# DONGLE01.net
KiCad netlist of a schematic drawn in Altium Designer
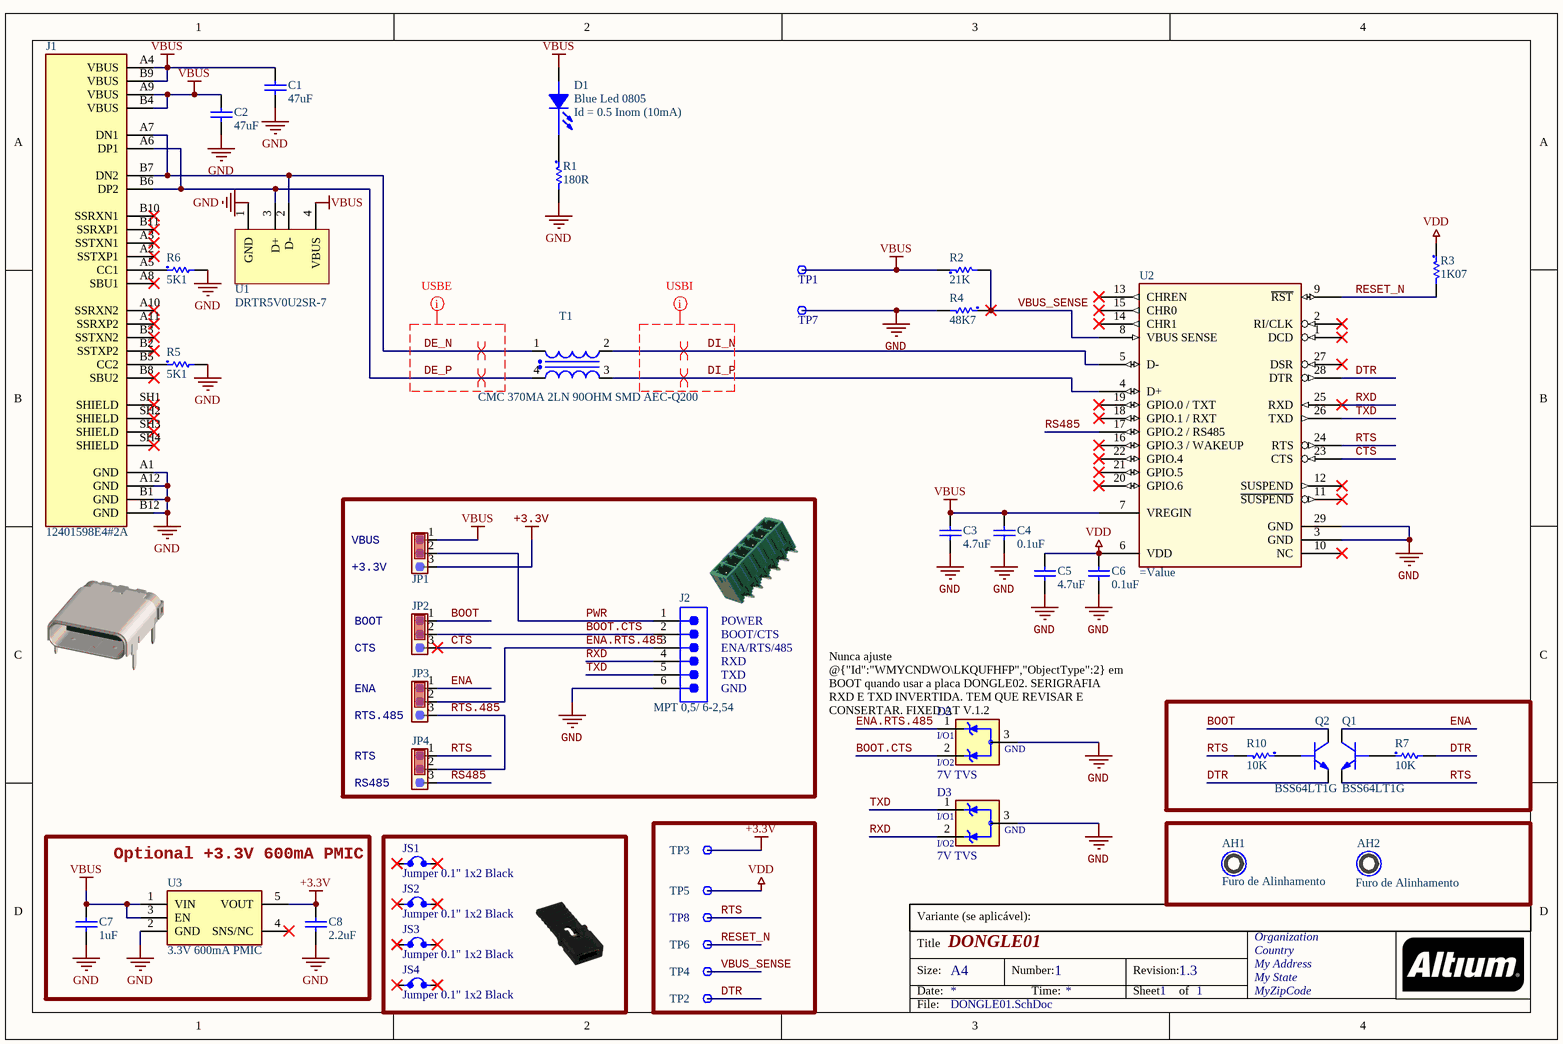
[diagram p0: DONGLE01.SchDoc]

(export (version "E")
  (design (tool "Eeschema 10.0.6"))
  (components
    (comp (ref "AH1")
      (value "Furo de Alinhamento")
      (footprint "AH_2.0MMD")
      (libsource (lib "My_Library") (part "Aligment Hole M2"))
    )
    (comp (ref "AH2")
      (value "Furo de Alinhamento")
      (footprint "AH_2.0MMD")
      (libsource (lib "My_Library") (part "Aligment Hole M2"))
    )
    (comp (ref "C1")
      (value "47uF")
      (footprint "C0805")
      (description "47 µF ±20% 10V Ceramic Capacitor X5R 0805 (2012 Metric)")
      (fields (field (name "MANUFACTURER") "Murata Electronics"))
      (libsource (lib "My_Library") (part "CAP"))
    )
    (comp (ref "C2")
      (value "47uF")
      (footprint "C0805")
      (description "47 µF ±20% 10V Ceramic Capacitor X5R 0805 (2012 Metric)")
      (fields (field (name "MANUFACTURER") "Murata Electronics"))
      (libsource (lib "My_Library") (part "CAP"))
    )
    (comp (ref "C3")
      (value "4.7uF")
      (footprint "C0805")
      (description "4.7 µF ±10% 50V Ceramic Capacitor X7R 0805 (2012 Metric)")
      (fields (field (name "MANUFACTURER") "TDK Corporation"))
      (libsource (lib "My_Library") (part "CAP"))
    )
    (comp (ref "C4")
      (value "0.1uF")
      (footprint "C0805")
      (description "0.1 µF ±10% 100V Ceramic Capacitor X7R 0805 (2012 Metric)")
      (fields (field (name "MANUFACTURER") "Murata Electronics"))
      (libsource (lib "My_Library") (part "CAP"))
    )
    (comp (ref "C5")
      (value "4.7uF")
      (footprint "C0805")
      (description "4.7 µF ±10% 50V Ceramic Capacitor X7R 0805 (2012 Metric)")
      (fields (field (name "MANUFACTURER") "TDK Corporation"))
      (libsource (lib "My_Library") (part "CAP"))
    )
    (comp (ref "C6")
      (value "0.1uF")
      (footprint "C0805")
      (description "0.1 µF ±10% 100V Ceramic Capacitor X7R 0805 (2012 Metric)")
      (fields (field (name "MANUFACTURER") "Murata Electronics"))
      (libsource (lib "My_Library") (part "CAP"))
    )
    (comp (ref "C7")
      (value "1uF")
      (footprint "C0805")
      (description "1 µF ±5% 16V Ceramic Capacitor X7R 0805 (2012 Metric)")
      (fields (field (name "MANUFACTURER") "KEMET"))
      (libsource (lib "My_Library") (part "CAP"))
    )
    (comp (ref "C8")
      (value "2.2uF")
      (footprint "C0805")
      (description "2.2 µF ±5% 16V Ceramic Capacitor X7R 0805 (2012 Metric)")
      (fields (field (name "MANUFACTURER") "KEMET"))
      (libsource (lib "My_Library") (part "CAP"))
    )
    (comp (ref "D1")
      (value "Blue Led 0805")
      (footprint "LED 0805")
      (description "Blue 470nm LED Indication - Discrete 3.2V 0805 (2012 Metric)")
      (fields (field (name "MANUFACTURER") "Würth Elektronik") (field (name "INFO") "Id = 0.5 Inom (10mA)"))
      (libsource (lib "My_Library") (part "LED GREEN 0805"))
    )
    (comp (ref "D2")
      (value "7V TVS")
      (footprint "WE-TVS_SOT23-3L")
      (description "7V Clamp 15A (8/20µs) Ipp Tvs Diode Surface Mount SOT-23-3")
      (fields (field (name "MANUFACTURER") "Würth Elektronik"))
      (libsource (lib "My_Library") (part "WE-TVS_SOT23-3L_824021"))
    )
    (comp (ref "D3")
      (value "7V TVS")
      (footprint "WE-TVS_SOT23-3L")
      (description "7V Clamp 15A (8/20µs) Ipp Tvs Diode Surface Mount SOT-23-3")
      (fields (field (name "MANUFACTURER") "Würth Elektronik"))
      (libsource (lib "My_Library") (part "WE-TVS_SOT23-3L_824021"))
    )
    (comp (ref "J1")
      (value "12401598E4#2A")
      (footprint "AMPHENOL_12401598E4#2A")
      (fields (field (name "MANUFACTURER") "Amphenol ICC"))
      (libsource (lib "My_Library") (part "12401598E4#2A"))
    )
    (comp (ref "J2")
      (value "MPT 0,5/ 6-2,54")
      (footprint "1725698")
      (description "6 Position Wire to Board Terminal Block Horizontal with Board 0.100\" (2.54mm) Through Hole")
      (fields (field (name "MANUFACTURER") "Phoenix Contact"))
      (libsource (lib "691101710002_Altium_WR-TBL_rev23c") (part "691322110006"))
    )
    (comp (ref "JP1")
      (value "Header 3 Pin")
      (footprint "JMP-3-PTH-180")
      (description "3 Pin Jumper")
      (fields (field (name "MANUFACTURER") "Würth Elektronik"))
      (libsource (lib "My_Library") (part "Jumper 3"))
    )
    (comp (ref "JP2")
      (value "Header 3 Pin")
      (footprint "JMP-3-PTH-180")
      (description "3 Pin Jumper")
      (fields (field (name "MANUFACTURER") "Würth Elektronik"))
      (libsource (lib "My_Library") (part "Jumper 3"))
    )
    (comp (ref "JP3")
      (value "Header 3 Pin")
      (footprint "JMP-3-PTH-180")
      (description "3 Pin Jumper")
      (fields (field (name "MANUFACTURER") "Würth Elektronik"))
      (libsource (lib "My_Library") (part "Jumper 3"))
    )
    (comp (ref "JP4")
      (value "Header 3 Pin")
      (footprint "JMP-3-PTH-180")
      (description "3 Pin Jumper")
      (fields (field (name "MANUFACTURER") "Würth Elektronik"))
      (libsource (lib "My_Library") (part "Jumper 3"))
    )
    (comp (ref "JS1")
      (value "Jumper 0.1\" 1x2 Black")
      (description "2 (1 x 2) Position Shunt Connector Open Top, Grip 0.100\" (2.54mm) Gold")
      (fields (field (name "MANUFACTURER") "Sullins Connector Solutions"))
      (libsource (lib "My_Library") (part "Jumper 2"))
    )
    (comp (ref "JS2")
      (value "Jumper 0.1\" 1x2 Black")
      (description "2 (1 x 2) Position Shunt Connector Open Top, Grip 0.100\" (2.54mm) Gold")
      (fields (field (name "MANUFACTURER") "Sullins Connector Solutions"))
      (libsource (lib "My_Library") (part "Jumper 2"))
    )
    (comp (ref "JS3")
      (value "Jumper 0.1\" 1x2 Black")
      (description "2 (1 x 2) Position Shunt Connector Open Top, Grip 0.100\" (2.54mm) Gold")
      (fields (field (name "MANUFACTURER") "Sullins Connector Solutions"))
      (libsource (lib "My_Library") (part "Jumper 2"))
    )
    (comp (ref "JS4")
      (value "Jumper 0.1\" 1x2 Black")
      (description "2 (1 x 2) Position Shunt Connector Open Top, Grip 0.100\" (2.54mm) Gold")
      (fields (field (name "MANUFACTURER") "Sullins Connector Solutions"))
      (libsource (lib "My_Library") (part "Jumper 2"))
    )
    (comp (ref "Q1")
      (value "BSS64LT1G")
      (footprint "SOT-23")
      (description "Bipolar (BJT) Transistor NPN 80 V 100 mA 60MHz 225 mW Surface Mount SOT-23-3 (TO-236)")
      (fields (field (name "MANUFACTURER") "onsemi"))
      (libsource (lib "My_Library") (part "TR-NPN-BC817-SOT23"))
    )
    (comp (ref "Q2")
      (value "BSS64LT1G")
      (footprint "SOT-23")
      (description "Bipolar (BJT) Transistor NPN 80 V 100 mA 60MHz 225 mW Surface Mount SOT-23-3 (TO-236)")
      (fields (field (name "MANUFACTURER") "onsemi"))
      (libsource (lib "My_Library") (part "TR-NPN-BC817-SOT23"))
    )
    (comp (ref "R1")
      (value "180R")
      (footprint "R0805")
      (description "180 Ohms ±1% 0.25W, 1/4W Chip Resistor 0805 (2012 Metric) Anti-Sulfur Thin Film")
      (fields (field (name "MANUFACTURER") "Stackpole Electronics Inc"))
      (libsource (lib "My_Library") (part "RESISTOR"))
    )
    (comp (ref "R2")
      (value "21K")
      (footprint "R0805")
      (description "21 kOhms ±1% 0.125W, 1/8W Chip Resistor 0805 (2012 Metric) Moisture Resistant Thick Film")
      (fields (field (name "MANUFACTURER") "YAGEO"))
      (libsource (lib "My_Library") (part "RESISTOR"))
    )
    (comp (ref "R3")
      (value "1K07")
      (footprint "R0805")
      (description "1.07 kOhms ±1% 0.125W, 1/8W Chip Resistor 0805 (2012 Metric) Automotive AEC-Q200 Thick Film")
      (fields (field (name "MANUFACTURER") "Vishay Dale"))
      (libsource (lib "My_Library") (part "RESISTOR"))
    )
    (comp (ref "R4")
      (value "48K7")
      (footprint "R0805")
      (description "48.7 kOhms ±1% 0.125W, 1/8W Chip Resistor 0805 (2012 Metric) Moisture Resistant Thick Film")
      (fields (field (name "MANUFACTURER") "YAGEO"))
      (libsource (lib "My_Library") (part "RESISTOR"))
    )
    (comp (ref "R5")
      (value "5K1")
      (footprint "R0805")
      (description "5.1 kOhms ±1% 0.125W, 1/8W Chip Resistor 0805 (2012 Metric) Moisture Resistant Thick Film")
      (fields (field (name "MANUFACTURER") "YAGEO"))
      (libsource (lib "My_Library") (part "RESISTOR"))
    )
    (comp (ref "R6")
      (value "5K1")
      (footprint "R0805")
      (description "5.1 kOhms ±1% 0.125W, 1/8W Chip Resistor 0805 (2012 Metric) Moisture Resistant Thick Film")
      (fields (field (name "MANUFACTURER") "YAGEO"))
      (libsource (lib "My_Library") (part "RESISTOR"))
    )
    (comp (ref "R7")
      (value "10K")
      (footprint "R0805")
      (description "10 kOhms ±1% 0.125W, 1/8W Chip Resistor 0805 (2012 Metric) Automotive AEC-Q200 Thick Film")
      (fields (field (name "MANUFACTURER") "Stackpole Electronics Inc"))
      (libsource (lib "My_Library") (part "RESISTOR"))
    )
    (comp (ref "R10")
      (value "10K")
      (footprint "R0805")
      (description "10 kOhms ±1% 0.125W, 1/8W Chip Resistor 0805 (2012 Metric) Automotive AEC-Q200 Thick Film")
      (fields (field (name "MANUFACTURER") "Stackpole Electronics Inc"))
      (libsource (lib "My_Library") (part "RESISTOR"))
    )
    (comp (ref "T1")
      (value "CMC 370MA 2LN 90OHM SMD AEC-Q200")
      (footprint "744232090")
      (description "2 Line Common Mode Choke Surface Mount 90 Ohms @ 100 MHz 370mA DCR 300mOhm")
      (fields (field (name "MANUFACTURER") "Würth Elektronik"))
      (libsource (lib "My_Library") (part "USB EMI FILTER"))
    )
    (comp (ref "TP1") (value "~") (footprint "TP") (libsource (lib "My_Library") (part "TESTPOINT")))
    (comp (ref "TP2") (value "~") (footprint "TP") (libsource (lib "My_Library") (part "TESTPOINT")))
    (comp (ref "TP3") (value "~") (footprint "TP") (libsource (lib "My_Library") (part "TESTPOINT")))
    (comp (ref "TP4") (value "~") (footprint "TP") (libsource (lib "My_Library") (part "TESTPOINT")))
    (comp (ref "TP5") (value "~") (footprint "TP") (libsource (lib "My_Library") (part "TESTPOINT")))
    (comp (ref "TP6") (value "~") (footprint "TP") (libsource (lib "My_Library") (part "TESTPOINT")))
    (comp (ref "TP7") (value "~") (footprint "TP") (libsource (lib "My_Library") (part "TESTPOINT")))
    (comp (ref "TP8") (value "~") (footprint "TP") (libsource (lib "My_Library") (part "TESTPOINT")))
    (comp (ref "U1")
      (value "USB ESD protection")
      (footprint "SOT143-4")
      (description "Clamp Ipp Tvs Diode Surface Mount SOT-143")
      (fields
        (field (name "MANUFACTURER P/N") "DRTR5V0U2SR-7")
        (field (name "MANUFACTURER") "Diodes Incorporated")
      )
      (libsource (lib "My_Library") (part "USB2.0_TVS_DIODES"))
    )
    (comp (ref "U2")
      (value "~")
      (footprint "QFN50P500X500X80_HS-29N CP2102N")
      (description "USB Bridge, USB to UART USB 2.0 UART Interface 28-QFN (5x5)")
      (fields (field (name "MANUFACTURER") "Silicon Labs"))
      (libsource (lib "My_Library") (part "CP2102N QFN28"))
    )
    (comp (ref "U3")
      (value "3.3V 600mA PMIC")
      (footprint "SOT94P280X100-5N")
      (description "Linear Voltage Regulator IC Positive Fixed 1 Output 600mA TSOT-23-5")
      (fields (field (name "MANUFACTURER") "Richtek USA Inc."))
      (libsource (lib "*") (part "RT9080-33GJ5"))
    )
  )
  (nets
    (net (code "1") (name "+3.3V") (class "Default")
      (node (ref "C8") (pin "1") (pinfunction "1_1") (pintype "passive"))
      (node (ref "JP1") (pin "3") (pinfunction "3_3") (pintype "passive"))
      (node (ref "TP3") (pin "1") (pinfunction "A_1") (pintype "passive"))
      (node (ref "U3") (pin "5") (pinfunction "VOUT_5") (pintype "power_in"))
    )
    (net (code "2") (name "/BOOT") (class "Default")
      (node (ref "JP2") (pin "1") (pinfunction "1_1") (pintype "passive"))
      (node (ref "Q2") (pin "3") (pinfunction "C_3") (pintype "passive"))
    )
    (net (code "3") (name "/BOOT.CTS") (class "Default")
      (node (ref "D2") (pin "2") (pinfunction "I/O2_2") (pintype "passive"))
      (node (ref "J2") (pin "2") (pinfunction "2_2") (pintype "passive"))
      (node (ref "JP2") (pin "2") (pinfunction "2_2") (pintype "passive"))
    )
    (net (code "4") (name "/CTS") (class "Default")
      (node (ref "JP2") (pin "3") (pinfunction "3_3") (pintype "passive"))
      (node (ref "U2") (pin "23") (pinfunction "CTS_23") (pintype "input"))
    )
    (net (code "5") (name "/DE_N") (class "Default")
      (node (ref "J1") (pin "A7") (pinfunction "DN1_A7") (pintype "passive"))
      (node (ref "J1") (pin "B7") (pinfunction "DN2_B7") (pintype "passive"))
      (node (ref "T1") (pin "1") (pinfunction "1_1") (pintype "passive"))
      (node (ref "U1") (pin "2") (pinfunction "D-_2") (pintype "passive"))
    )
    (net (code "6") (name "/DE_P") (class "Default")
      (node (ref "J1") (pin "A6") (pinfunction "DP1_A6") (pintype "passive"))
      (node (ref "J1") (pin "B6") (pinfunction "DP2_B6") (pintype "passive"))
      (node (ref "T1") (pin "4") (pinfunction "4_4") (pintype "passive"))
      (node (ref "U1") (pin "3") (pinfunction "D+_3") (pintype "passive"))
    )
    (net (code "7") (name "/DI_N") (class "Default")
      (node (ref "T1") (pin "2") (pinfunction "2_2") (pintype "passive"))
      (node (ref "U2") (pin "5") (pinfunction "D-_5") (pintype "bidirectional"))
    )
    (net (code "8") (name "/DI_P") (class "Default")
      (node (ref "T1") (pin "3") (pinfunction "3_3") (pintype "passive"))
      (node (ref "U2") (pin "4") (pinfunction "D+_4") (pintype "bidirectional"))
    )
    (net (code "9") (name "/DTR") (class "Default")
      (node (ref "Q2") (pin "2") (pinfunction "E_2") (pintype "passive"))
      (node (ref "R7") (pin "2") (pinfunction "2_2") (pintype "passive"))
      (node (ref "TP2") (pin "1") (pinfunction "A_1") (pintype "passive"))
      (node (ref "U2") (pin "28") (pinfunction "DTR_28") (pintype "output"))
    )
    (net (code "10") (name "/ENA") (class "Default")
      (node (ref "JP3") (pin "1") (pinfunction "1_1") (pintype "passive"))
      (node (ref "Q1") (pin "3") (pinfunction "C_3") (pintype "passive"))
    )
    (net (code "11") (name "/ENA.RTS.485") (class "Default")
      (node (ref "D2") (pin "1") (pinfunction "I/O1_1") (pintype "passive"))
      (node (ref "J2") (pin "3") (pinfunction "3_3") (pintype "passive"))
      (node (ref "JP3") (pin "2") (pinfunction "2_2") (pintype "passive"))
    )
    (net (code "12") (name "/PWR") (class "Default")
      (node (ref "J2") (pin "1") (pinfunction "1_1") (pintype "passive"))
      (node (ref "JP1") (pin "2") (pinfunction "2_2") (pintype "passive"))
    )
    (net (code "13") (name "/RESET_N") (class "Default")
      (node (ref "R3") (pin "2") (pinfunction "2_2") (pintype "passive"))
      (node (ref "TP6") (pin "1") (pinfunction "A_1") (pintype "passive"))
      (node (ref "U2") (pin "9") (pinfunction "~{RST}_9") (pintype "bidirectional"))
    )
    (net (code "14") (name "/RS485") (class "Default")
      (node (ref "JP4") (pin "3") (pinfunction "3_3") (pintype "passive"))
      (node (ref "U2") (pin "17") (pinfunction "GPIO.2_/_RS485_17") (pintype "bidirectional"))
    )
    (net (code "15") (name "/RTS") (class "Default")
      (node (ref "JP4") (pin "1") (pinfunction "1_1") (pintype "passive"))
      (node (ref "Q1") (pin "2") (pinfunction "E_2") (pintype "passive"))
      (node (ref "R10") (pin "2") (pinfunction "2_2") (pintype "passive"))
      (node (ref "TP8") (pin "1") (pinfunction "A_1") (pintype "passive"))
      (node (ref "U2") (pin "24") (pinfunction "RTS_24") (pintype "output"))
    )
    (net (code "16") (name "/RTS.485") (class "Default")
      (node (ref "JP3") (pin "3") (pinfunction "3_3") (pintype "passive"))
      (node (ref "JP4") (pin "2") (pinfunction "2_2") (pintype "passive"))
    )
    (net (code "17") (name "/RXD") (class "Default")
      (node (ref "D3") (pin "2") (pinfunction "I/O2_2") (pintype "passive"))
      (node (ref "J2") (pin "4") (pinfunction "4_4") (pintype "passive"))
      (node (ref "U2") (pin "25") (pinfunction "RXD_25") (pintype "input"))
    )
    (net (code "18") (name "/TXD") (class "Default")
      (node (ref "D3") (pin "1") (pinfunction "I/O1_1") (pintype "passive"))
      (node (ref "J2") (pin "5") (pinfunction "5_5") (pintype "passive"))
      (node (ref "U2") (pin "26") (pinfunction "TXD_26") (pintype "output"))
    )
    (net (code "19") (name "/VBUS_SENSE") (class "Default")
      (node (ref "R2") (pin "2") (pinfunction "2_2") (pintype "passive"))
      (node (ref "R4") (pin "1") (pinfunction "1_1") (pintype "passive"))
      (node (ref "TP4") (pin "1") (pinfunction "A_1") (pintype "passive"))
      (node (ref "U2") (pin "8") (pinfunction "VBUS_SENSE_8") (pintype "input"))
    )
    (net (code "20") (name "GND") (class "Default")
      (node (ref "C1") (pin "2") (pinfunction "2_2") (pintype "passive"))
      (node (ref "C2") (pin "2") (pinfunction "2_2") (pintype "passive"))
      (node (ref "C3") (pin "2") (pinfunction "2_2") (pintype "passive"))
      (node (ref "C4") (pin "2") (pinfunction "2_2") (pintype "passive"))
      (node (ref "C5") (pin "2") (pinfunction "2_2") (pintype "passive"))
      (node (ref "C6") (pin "2") (pinfunction "2_2") (pintype "passive"))
      (node (ref "C7") (pin "2") (pinfunction "2_2") (pintype "passive"))
      (node (ref "C8") (pin "2") (pinfunction "2_2") (pintype "passive"))
      (node (ref "D2") (pin "3") (pinfunction "GND_3") (pintype "passive"))
      (node (ref "D3") (pin "3") (pinfunction "GND_3") (pintype "passive"))
      (node (ref "J1") (pin "A1") (pinfunction "GND_A1") (pintype "power_in"))
      (node (ref "J1") (pin "A12") (pinfunction "GND_A12") (pintype "power_in"))
      (node (ref "J1") (pin "B1") (pinfunction "GND_B1") (pintype "power_in"))
      (node (ref "J1") (pin "B12") (pinfunction "GND_B12") (pintype "power_in"))
      (node (ref "J2") (pin "6") (pinfunction "6_6") (pintype "passive"))
      (node (ref "R1") (pin "2") (pinfunction "2_2") (pintype "passive"))
      (node (ref "R4") (pin "2") (pinfunction "2_2") (pintype "passive"))
      (node (ref "R5") (pin "2") (pinfunction "2_2") (pintype "passive"))
      (node (ref "R6") (pin "2") (pinfunction "2_2") (pintype "passive"))
      (node (ref "TP7") (pin "1") (pinfunction "A_1") (pintype "passive"))
      (node (ref "U1") (pin "1") (pinfunction "GND_1") (pintype "power_in"))
      (node (ref "U2") (pin "29") (pinfunction "GND_29") (pintype "power_in"))
      (node (ref "U2") (pin "3") (pinfunction "GND_3") (pintype "power_in"))
      (node (ref "U3") (pin "2") (pinfunction "GND_2") (pintype "power_in"))
    )
    (net (code "21") (name "Net-(D1-PadK)") (class "Default")
      (node (ref "D1") (pin "K") (pinfunction "K_K") (pintype "passive"))
      (node (ref "R1") (pin "1") (pinfunction "1_1") (pintype "passive"))
    )
    (net (code "22") (name "Net-(J1-CC1)") (class "Default")
      (node (ref "J1") (pin "A5") (pinfunction "CC1_A5") (pintype "passive"))
      (node (ref "R6") (pin "1") (pinfunction "1_1") (pintype "passive"))
    )
    (net (code "23") (name "Net-(J1-CC2)") (class "Default")
      (node (ref "J1") (pin "B5") (pinfunction "CC2_B5") (pintype "passive"))
      (node (ref "R5") (pin "1") (pinfunction "1_1") (pintype "passive"))
    )
    (net (code "24") (name "Net-(Q1-B)") (class "Default")
      (node (ref "Q1") (pin "1") (pinfunction "B_1") (pintype "passive"))
      (node (ref "R7") (pin "1") (pinfunction "1_1") (pintype "passive"))
    )
    (net (code "25") (name "Net-(Q2-B)") (class "Default")
      (node (ref "Q2") (pin "1") (pinfunction "B_1") (pintype "passive"))
      (node (ref "R10") (pin "1") (pinfunction "1_1") (pintype "passive"))
    )
    (net (code "26") (name "VBUS") (class "Default")
      (node (ref "C1") (pin "1") (pinfunction "1_1") (pintype "passive"))
      (node (ref "C2") (pin "1") (pinfunction "1_1") (pintype "passive"))
      (node (ref "C3") (pin "1") (pinfunction "1_1") (pintype "passive"))
      (node (ref "C4") (pin "1") (pinfunction "1_1") (pintype "passive"))
      (node (ref "C7") (pin "1") (pinfunction "1_1") (pintype "passive"))
      (node (ref "D1") (pin "A") (pinfunction "A_A") (pintype "passive"))
      (node (ref "J1") (pin "A4") (pinfunction "VBUS_A4") (pintype "power_in"))
      (node (ref "J1") (pin "A9") (pinfunction "VBUS_A9") (pintype "power_in"))
      (node (ref "J1") (pin "B4") (pinfunction "VBUS_B4") (pintype "power_in"))
      (node (ref "J1") (pin "B9") (pinfunction "VBUS_B9") (pintype "power_in"))
      (node (ref "JP1") (pin "1") (pinfunction "1_1") (pintype "passive"))
      (node (ref "R2") (pin "1") (pinfunction "1_1") (pintype "passive"))
      (node (ref "TP1") (pin "1") (pinfunction "A_1") (pintype "passive"))
      (node (ref "U1") (pin "4") (pinfunction "VBUS_4") (pintype "power_in"))
      (node (ref "U2") (pin "7") (pinfunction "VREGIN_7") (pintype "power_in"))
      (node (ref "U3") (pin "1") (pinfunction "VIN_1") (pintype "power_in"))
      (node (ref "U3") (pin "3") (pinfunction "EN_3") (pintype "passive"))
    )
    (net (code "27") (name "VDD") (class "Default")
      (node (ref "C5") (pin "1") (pinfunction "1_1") (pintype "passive"))
      (node (ref "C6") (pin "1") (pinfunction "1_1") (pintype "passive"))
      (node (ref "R3") (pin "1") (pinfunction "1_1") (pintype "passive"))
      (node (ref "TP5") (pin "1") (pinfunction "A_1") (pintype "passive"))
      (node (ref "U2") (pin "6") (pinfunction "VDD_6") (pintype "power_in"))
    )
    (net (code "28") (name "unconnected-(J1-SBU1-PadA8)") (class "Default")
      (node (ref "J1") (pin "A8") (pinfunction "SBU1_A8") (pintype "passive+no_connect"))
    )
    (net (code "29") (name "unconnected-(J1-SBU2-PadB8)") (class "Default")
      (node (ref "J1") (pin "B8") (pinfunction "SBU2_B8") (pintype "passive+no_connect"))
    )
    (net (code "30") (name "unconnected-(J1-SHIELD-PadSH1)") (class "Default")
      (node (ref "J1") (pin "SH1") (pinfunction "SHIELD_SH1") (pintype "power_in+no_connect"))
    )
    (net (code "31") (name "unconnected-(J1-SHIELD-PadSH2)") (class "Default")
      (node (ref "J1") (pin "SH2") (pinfunction "SHIELD_SH2") (pintype "power_in+no_connect"))
    )
    (net (code "32") (name "unconnected-(J1-SHIELD-PadSH3)") (class "Default")
      (node (ref "J1") (pin "SH3") (pinfunction "SHIELD_SH3") (pintype "power_in+no_connect"))
    )
    (net (code "33") (name "unconnected-(J1-SHIELD-PadSH4)") (class "Default")
      (node (ref "J1") (pin "SH4") (pinfunction "SHIELD_SH4") (pintype "power_in+no_connect"))
    )
    (net (code "34") (name "unconnected-(J1-SSRXN1-PadB10)") (class "Default")
      (node (ref "J1") (pin "B10") (pinfunction "SSRXN1_B10") (pintype "passive+no_connect"))
    )
    (net (code "35") (name "unconnected-(J1-SSRXN2-PadA10)") (class "Default")
      (node (ref "J1") (pin "A10") (pinfunction "SSRXN2_A10") (pintype "passive+no_connect"))
    )
    (net (code "36") (name "unconnected-(J1-SSRXP1-PadB11)") (class "Default")
      (node (ref "J1") (pin "B11") (pinfunction "SSRXP1_B11") (pintype "passive+no_connect"))
    )
    (net (code "37") (name "unconnected-(J1-SSRXP2-PadA11)") (class "Default")
      (node (ref "J1") (pin "A11") (pinfunction "SSRXP2_A11") (pintype "passive+no_connect"))
    )
    (net (code "38") (name "unconnected-(J1-SSTXN1-PadA3)") (class "Default")
      (node (ref "J1") (pin "A3") (pinfunction "SSTXN1_A3") (pintype "passive+no_connect"))
    )
    (net (code "39") (name "unconnected-(J1-SSTXN2-PadB3)") (class "Default")
      (node (ref "J1") (pin "B3") (pinfunction "SSTXN2_B3") (pintype "passive+no_connect"))
    )
    (net (code "40") (name "unconnected-(J1-SSTXP1-PadA2)") (class "Default")
      (node (ref "J1") (pin "A2") (pinfunction "SSTXP1_A2") (pintype "passive+no_connect"))
    )
    (net (code "41") (name "unconnected-(J1-SSTXP2-PadB2)") (class "Default")
      (node (ref "J1") (pin "B2") (pinfunction "SSTXP2_B2") (pintype "passive+no_connect"))
    )
    (net (code "42") (name "unconnected-(JS1-Pad1)") (class "Default")
      (node (ref "JS1") (pin "1") (pinfunction "1_1") (pintype "passive+no_connect"))
    )
    (net (code "43") (name "unconnected-(JS1-Pad2)") (class "Default")
      (node (ref "JS1") (pin "2") (pinfunction "2_2") (pintype "passive+no_connect"))
    )
    (net (code "44") (name "unconnected-(JS2-Pad1)") (class "Default")
      (node (ref "JS2") (pin "1") (pinfunction "1_1") (pintype "passive+no_connect"))
    )
    (net (code "45") (name "unconnected-(JS2-Pad2)") (class "Default")
      (node (ref "JS2") (pin "2") (pinfunction "2_2") (pintype "passive+no_connect"))
    )
    (net (code "46") (name "unconnected-(JS3-Pad1)") (class "Default")
      (node (ref "JS3") (pin "1") (pinfunction "1_1") (pintype "passive+no_connect"))
    )
    (net (code "47") (name "unconnected-(JS3-Pad2)") (class "Default")
      (node (ref "JS3") (pin "2") (pinfunction "2_2") (pintype "passive+no_connect"))
    )
    (net (code "48") (name "unconnected-(JS4-Pad1)") (class "Default")
      (node (ref "JS4") (pin "1") (pinfunction "1_1") (pintype "passive+no_connect"))
    )
    (net (code "49") (name "unconnected-(JS4-Pad2)") (class "Default")
      (node (ref "JS4") (pin "2") (pinfunction "2_2") (pintype "passive+no_connect"))
    )
    (net (code "50") (name "unconnected-(U2-CHR0-Pad15)") (class "Default")
      (node (ref "U2") (pin "15") (pinfunction "CHR0_15") (pintype "output+no_connect"))
    )
    (net (code "51") (name "unconnected-(U2-CHR1-Pad14)") (class "Default")
      (node (ref "U2") (pin "14") (pinfunction "CHR1_14") (pintype "output+no_connect"))
    )
    (net (code "52") (name "unconnected-(U2-CHREN-Pad13)") (class "Default")
      (node (ref "U2") (pin "13") (pinfunction "CHREN_13") (pintype "output+no_connect"))
    )
    (net (code "53") (name "unconnected-(U2-DCD-Pad1)") (class "Default")
      (node (ref "U2") (pin "1") (pinfunction "DCD_1") (pintype "input+no_connect"))
    )
    (net (code "54") (name "unconnected-(U2-DSR-Pad27)") (class "Default")
      (node (ref "U2") (pin "27") (pinfunction "DSR_27") (pintype "input+no_connect"))
    )
    (net (code "55") (name "unconnected-(U2-GPIO.0_{slash}_TXT-Pad19)") (class "Default")
      (node (ref "U2") (pin "19") (pinfunction "GPIO.0_/_TXT_19") (pintype "bidirectional+no_connect"))
    )
    (net (code "56") (name "unconnected-(U2-GPIO.1_{slash}_RXT-Pad18)") (class "Default")
      (node (ref "U2") (pin "18") (pinfunction "GPIO.1_/_RXT_18") (pintype "bidirectional+no_connect"))
    )
    (net (code "57") (name "unconnected-(U2-GPIO.3_{slash}_WAKEUP-Pad16)") (class "Default")
      (node (ref "U2") (pin "16") (pinfunction "GPIO.3_/_WAKEUP_16") (pintype "bidirectional+no_connect"))
    )
    (net (code "58") (name "unconnected-(U2-GPIO.4-Pad22)") (class "Default")
      (node (ref "U2") (pin "22") (pinfunction "GPIO.4_22") (pintype "bidirectional+no_connect"))
    )
    (net (code "59") (name "unconnected-(U2-GPIO.5-Pad21)") (class "Default")
      (node (ref "U2") (pin "21") (pinfunction "GPIO.5_21") (pintype "bidirectional+no_connect"))
    )
    (net (code "60") (name "unconnected-(U2-GPIO.6-Pad20)") (class "Default")
      (node (ref "U2") (pin "20") (pinfunction "GPIO.6_20") (pintype "bidirectional+no_connect"))
    )
    (net (code "61") (name "unconnected-(U2-NC-Pad10)") (class "Default")
      (node (ref "U2") (pin "10") (pinfunction "NC_10") (pintype "passive+no_connect"))
    )
    (net (code "62") (name "unconnected-(U2-RI{slash}CLK-Pad2)") (class "Default")
      (node (ref "U2") (pin "2") (pinfunction "RI/CLK_2") (pintype "input+no_connect"))
    )
    (net (code "63") (name "unconnected-(U2-SUSPEND-Pad12)") (class "Default")
      (node (ref "U2") (pin "12") (pinfunction "SUSPEND_12") (pintype "output+no_connect"))
    )
    (net (code "64") (name "unconnected-(U2-~{SUSPEND}-Pad11)") (class "Default")
      (node (ref "U2") (pin "11") (pinfunction "~{SUSPEND}_11") (pintype "output+no_connect"))
    )
    (net (code "65") (name "unconnected-(U3-SNS{slash}NC-Pad4)") (class "Default")
      (node (ref "U3") (pin "4") (pinfunction "SNS/NC_4") (pintype "passive+no_connect"))
    )
  )
)
